# Power_Distribution_-_Display.net
KiCad netlist of a schematic drawn in Altium Designer
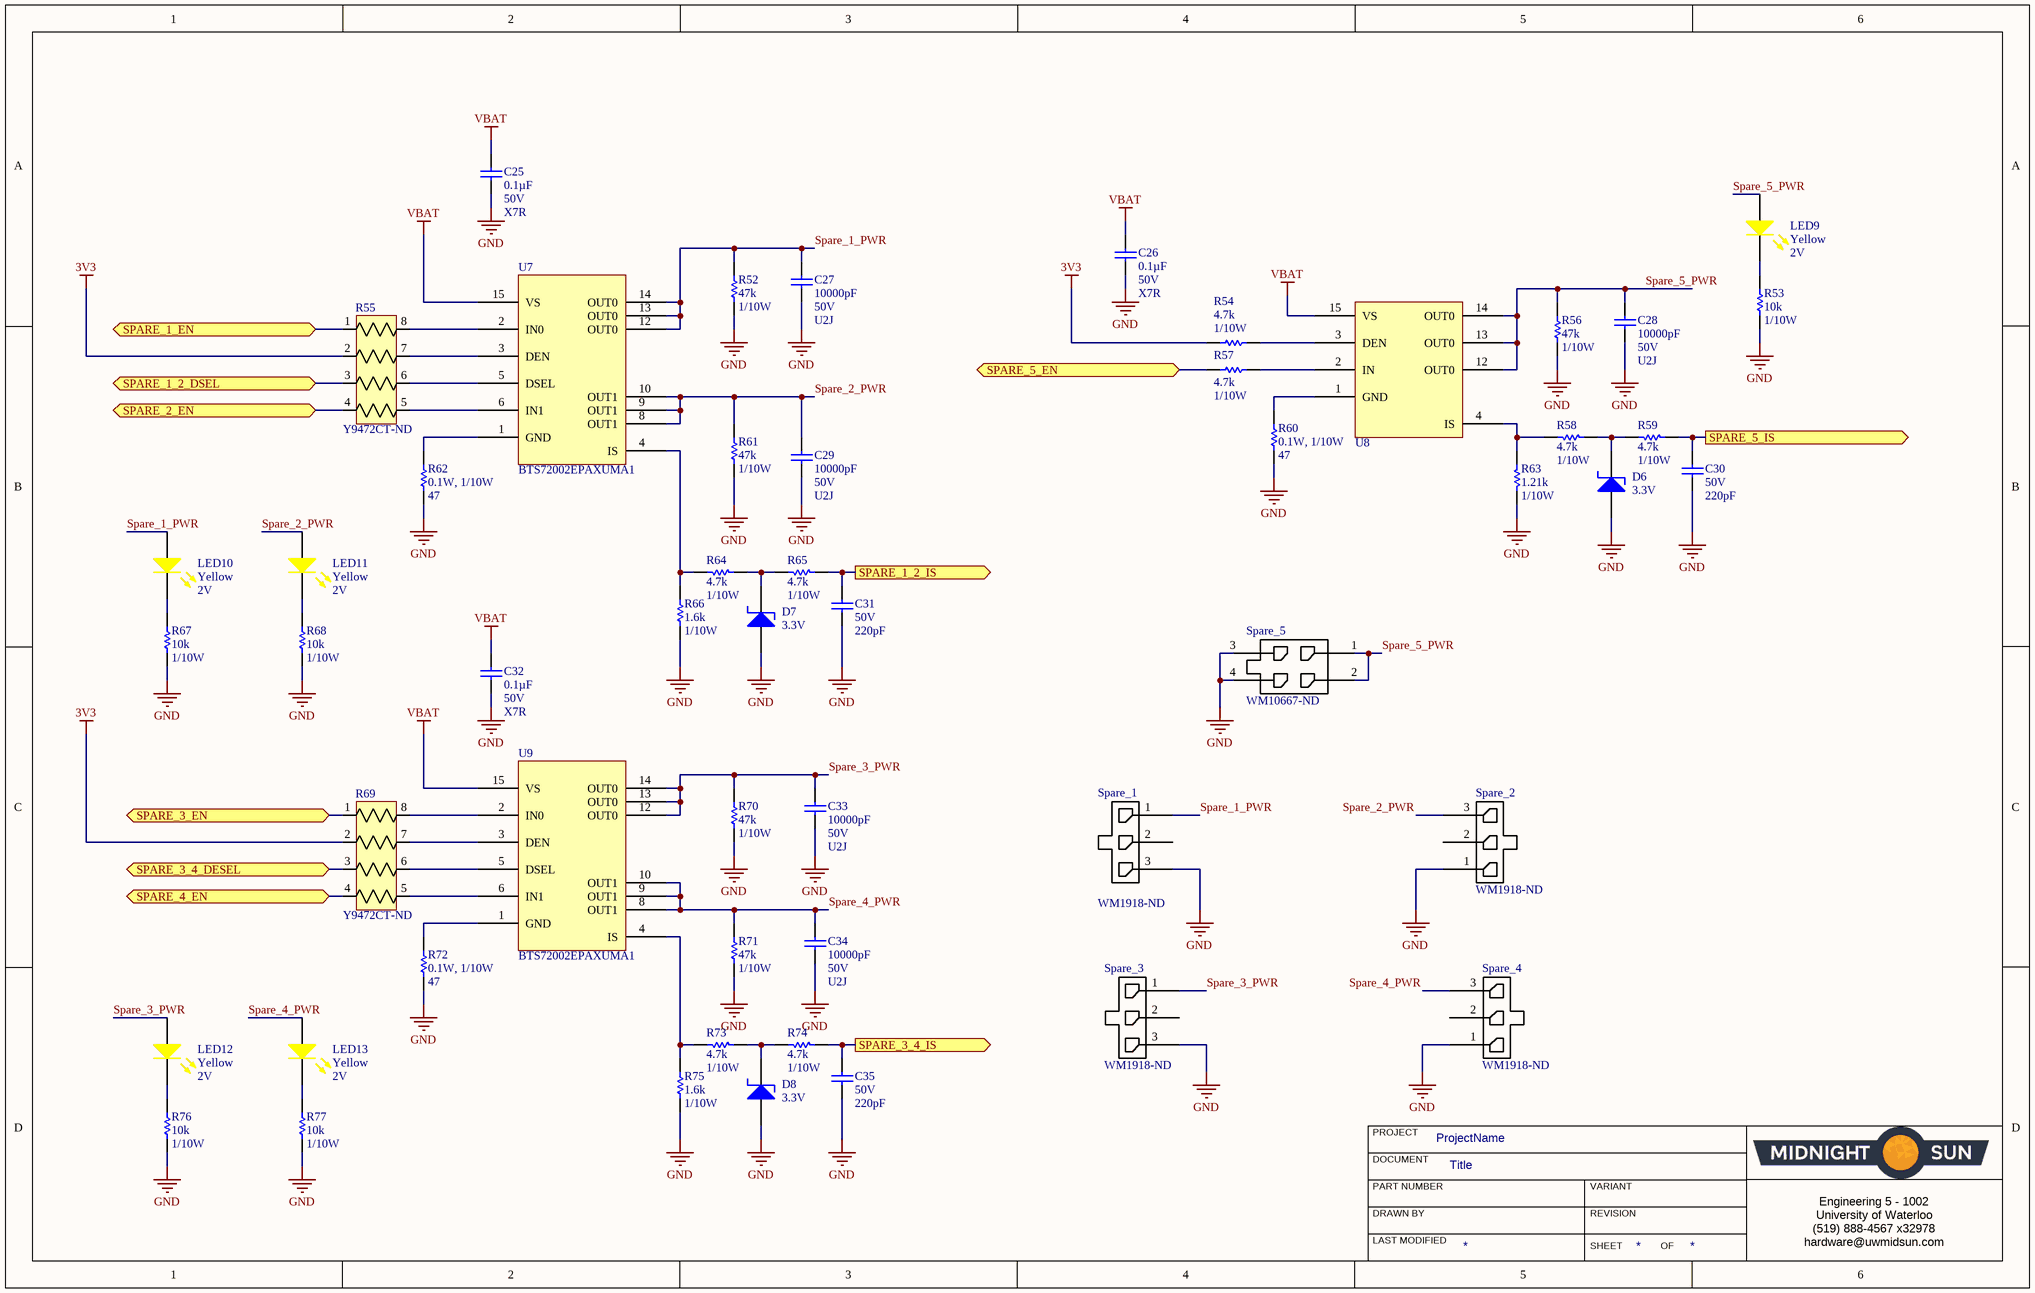
[diagram p0: Power Distribution - Display.SchDoc]

(export (version "E")
  (design (tool "Eeschema 10.0.6"))
  (components
    (comp (ref "C25")
      (value "CAP CER 0.1UF 50V 10% X7R 0603")
      (footprint "CAP, 0603")
      (description "0.10µF ±10% 50V Ceramic Capacitor X7R 0603 (1608 Metric)")
      (fields
        (field (name "TOLERANCE") "±10%")
        (field (name "CAPACITANCE") "0.1µF")
        (field (name "VOLTAGE") "50V")
        (field (name "TEMPERATURE COEFFICIENT") "X7R")
      )
      (libsource (lib "Schematic Diagrams") (part "CAP CER 0.1UF 50V 10% X7R 0603"))
    )
    (comp (ref "C26")
      (value "CAP CER 0.1UF 50V 10% X7R 0603")
      (footprint "CAP, 0603")
      (description "0.10µF ±10% 50V Ceramic Capacitor X7R 0603 (1608 Metric)")
      (fields
        (field (name "TOLERANCE") "±10%")
        (field (name "CAPACITANCE") "0.1µF")
        (field (name "VOLTAGE") "50V")
        (field (name "TEMPERATURE COEFFICIENT") "X7R")
      )
      (libsource (lib "Schematic Diagrams") (part "CAP CER 0.1UF 50V 10% X7R 0603"))
    )
    (comp (ref "C27")
      (value "CAP CER 10nF 50V 5% X7R 0603")
      (footprint "CAP, 0603")
      (description "10000pF ±5% 50V Ceramic Capacitor U2J 0603 (1608 Metric)")
      (fields
        (field (name "TOLERANCE") "±5%")
        (field (name "CAPACITANCE") "10000pF")
        (field (name "VOLTAGE") "50V")
        (field (name "TEMPERATURE COEFFICIENT") "U2J")
      )
      (libsource (lib "Schematic Diagrams") (part "CAP CER 10nF 50V 5% X7R 0603"))
    )
    (comp (ref "C28")
      (value "CAP CER 10nF 50V 5% X7R 0603")
      (footprint "CAP, 0603")
      (description "10000pF ±5% 50V Ceramic Capacitor U2J 0603 (1608 Metric)")
      (fields
        (field (name "TOLERANCE") "±5%")
        (field (name "CAPACITANCE") "10000pF")
        (field (name "VOLTAGE") "50V")
        (field (name "TEMPERATURE COEFFICIENT") "U2J")
      )
      (libsource (lib "Schematic Diagrams") (part "CAP CER 10nF 50V 5% X7R 0603"))
    )
    (comp (ref "C29")
      (value "CAP CER 10nF 50V 5% X7R 0603")
      (footprint "CAP, 0603")
      (description "10000pF ±5% 50V Ceramic Capacitor U2J 0603 (1608 Metric)")
      (fields
        (field (name "TOLERANCE") "±5%")
        (field (name "CAPACITANCE") "10000pF")
        (field (name "VOLTAGE") "50V")
        (field (name "TEMPERATURE COEFFICIENT") "U2J")
      )
      (libsource (lib "Schematic Diagrams") (part "CAP CER 10nF 50V 5% X7R 0603"))
    )
    (comp (ref "C30")
      (value "CAP CER 220PF 50V C0G/NP0 0603")
      (footprint "CAP, 0603")
      (description "220pF ±5% 50V Ceramic Capacitor C0G, NP0 0603 (1608 Metric)")
      (fields
        (field (name "MANUFACTURER") "KEMET")
        (field (name "TOLERANCE") "5%")
        (field (name "VOLTAGE RATING") "50V")
        (field (name "CAPACITANCE") "220pF")
      )
      (libsource (lib "Schematic Diagrams") (part "CAP CER 220PF 50V C0G/NP0 0603"))
    )
    (comp (ref "C31")
      (value "CAP CER 220PF 50V C0G/NP0 0603")
      (footprint "CAP, 0603")
      (description "220pF ±5% 50V Ceramic Capacitor C0G, NP0 0603 (1608 Metric)")
      (fields
        (field (name "MANUFACTURER") "KEMET")
        (field (name "TOLERANCE") "5%")
        (field (name "VOLTAGE RATING") "50V")
        (field (name "CAPACITANCE") "220pF")
      )
      (libsource (lib "Schematic Diagrams") (part "CAP CER 220PF 50V C0G/NP0 0603"))
    )
    (comp (ref "C32")
      (value "CAP CER 0.1UF 50V 10% X7R 0603")
      (footprint "CAP, 0603")
      (description "0.10µF ±10% 50V Ceramic Capacitor X7R 0603 (1608 Metric)")
      (fields
        (field (name "TOLERANCE") "±10%")
        (field (name "CAPACITANCE") "0.1µF")
        (field (name "VOLTAGE") "50V")
        (field (name "TEMPERATURE COEFFICIENT") "X7R")
      )
      (libsource (lib "Schematic Diagrams") (part "CAP CER 0.1UF 50V 10% X7R 0603"))
    )
    (comp (ref "C33")
      (value "CAP CER 10nF 50V 5% X7R 0603")
      (footprint "CAP, 0603")
      (description "10000pF ±5% 50V Ceramic Capacitor U2J 0603 (1608 Metric)")
      (fields
        (field (name "TOLERANCE") "±5%")
        (field (name "CAPACITANCE") "10000pF")
        (field (name "VOLTAGE") "50V")
        (field (name "TEMPERATURE COEFFICIENT") "U2J")
      )
      (libsource (lib "Schematic Diagrams") (part "CAP CER 10nF 50V 5% X7R 0603"))
    )
    (comp (ref "C34")
      (value "CAP CER 10nF 50V 5% X7R 0603")
      (footprint "CAP, 0603")
      (description "10000pF ±5% 50V Ceramic Capacitor U2J 0603 (1608 Metric)")
      (fields
        (field (name "TOLERANCE") "±5%")
        (field (name "CAPACITANCE") "10000pF")
        (field (name "VOLTAGE") "50V")
        (field (name "TEMPERATURE COEFFICIENT") "U2J")
      )
      (libsource (lib "Schematic Diagrams") (part "CAP CER 10nF 50V 5% X7R 0603"))
    )
    (comp (ref "C35")
      (value "CAP CER 220PF 50V C0G/NP0 0603")
      (footprint "CAP, 0603")
      (description "220pF ±5% 50V Ceramic Capacitor C0G, NP0 0603 (1608 Metric)")
      (fields
        (field (name "MANUFACTURER") "KEMET")
        (field (name "TOLERANCE") "5%")
        (field (name "VOLTAGE RATING") "50V")
        (field (name "CAPACITANCE") "220pF")
      )
      (libsource (lib "Schematic Diagrams") (part "CAP CER 220PF 50V C0G/NP0 0603"))
    )
    (comp (ref "D6")
      (value "DIODE ZENER 3.3V 200MW SOD323")
      (footprint "sod-323")
      (description "Zener Diode 3.3V 200mW ±5% Surface Mount SOD-323")
      (fields (field (name "VOLTAGE") "3.3V"))
      (libsource (lib "Schematic Diagrams") (part "DIODE ZENER 3.3V 200MW SOD323"))
    )
    (comp (ref "D7")
      (value "DIODE ZENER 3.3V 200MW SOD323")
      (footprint "sod-323")
      (description "Zener Diode 3.3V 200mW ±5% Surface Mount SOD-323")
      (fields (field (name "VOLTAGE") "3.3V"))
      (libsource (lib "Schematic Diagrams") (part "DIODE ZENER 3.3V 200MW SOD323"))
    )
    (comp (ref "D8")
      (value "DIODE ZENER 3.3V 200MW SOD323")
      (footprint "sod-323")
      (description "Zener Diode 3.3V 200mW ±5% Surface Mount SOD-323")
      (fields (field (name "VOLTAGE") "3.3V"))
      (libsource (lib "Schematic Diagrams") (part "DIODE ZENER 3.3V 200MW SOD323"))
    )
    (comp (ref "LED9")
      (value "LED YELLOW CLEAR 2.1V 0603")
      (footprint "LED_0603")
      (description "Yellow 590nm LED Indication - Discrete 2V 0603 (1608 Metric)")
      (fields
        (field (name "MANUFACTURER") "Wurth Electronics Inc.")
        (field (name "MANUFACTURER PART NUMBER") "150060YS75000")
        (field (name "COLOR") "Yellow")
        (field (name "VOLTAGE - FORWARD (VF) (TYP)") "2V")
      )
      (libsource (lib "Schematic Diagrams") (part "LED YELLOW CLEAR 2.1V 0603"))
    )
    (comp (ref "LED10")
      (value "LED YELLOW CLEAR 2.1V 0603")
      (footprint "LED_0603")
      (description "Yellow 590nm LED Indication - Discrete 2V 0603 (1608 Metric)")
      (fields
        (field (name "MANUFACTURER") "Wurth Electronics Inc.")
        (field (name "MANUFACTURER PART NUMBER") "150060YS75000")
        (field (name "COLOR") "Yellow")
        (field (name "VOLTAGE - FORWARD (VF) (TYP)") "2V")
      )
      (libsource (lib "Schematic Diagrams") (part "LED YELLOW CLEAR 2.1V 0603"))
    )
    (comp (ref "LED11")
      (value "LED YELLOW CLEAR 2.1V 0603")
      (footprint "LED_0603")
      (description "Yellow 590nm LED Indication - Discrete 2V 0603 (1608 Metric)")
      (fields
        (field (name "MANUFACTURER") "Wurth Electronics Inc.")
        (field (name "MANUFACTURER PART NUMBER") "150060YS75000")
        (field (name "COLOR") "Yellow")
        (field (name "VOLTAGE - FORWARD (VF) (TYP)") "2V")
      )
      (libsource (lib "Schematic Diagrams") (part "LED YELLOW CLEAR 2.1V 0603"))
    )
    (comp (ref "LED12")
      (value "LED YELLOW CLEAR 2.1V 0603")
      (footprint "LED_0603")
      (description "Yellow 590nm LED Indication - Discrete 2V 0603 (1608 Metric)")
      (fields
        (field (name "MANUFACTURER") "Wurth Electronics Inc.")
        (field (name "MANUFACTURER PART NUMBER") "150060YS75000")
        (field (name "COLOR") "Yellow")
        (field (name "VOLTAGE - FORWARD (VF) (TYP)") "2V")
      )
      (libsource (lib "Schematic Diagrams") (part "LED YELLOW CLEAR 2.1V 0603"))
    )
    (comp (ref "LED13")
      (value "LED YELLOW CLEAR 2.1V 0603")
      (footprint "LED_0603")
      (description "Yellow 590nm LED Indication - Discrete 2V 0603 (1608 Metric)")
      (fields
        (field (name "MANUFACTURER") "Wurth Electronics Inc.")
        (field (name "MANUFACTURER PART NUMBER") "150060YS75000")
        (field (name "COLOR") "Yellow")
        (field (name "VOLTAGE - FORWARD (VF) (TYP)") "2V")
      )
      (libsource (lib "Schematic Diagrams") (part "LED YELLOW CLEAR 2.1V 0603"))
    )
    (comp (ref "R52")
      (value "RES 47K OHM 1% 1/10W 0603")
      (footprint "RES, 0603")
      (description "47 kOhms ±1% 0.1W, 1/10W Chip Resistor 0603 (1608 Metric) Automotive AEC-Q200 Thick Film")
      (fields
        (field (name "MANUFACTURER") "Panasonic")
        (field (name "MANUFACTURER PART NUMBER") "ERJ3EKF4702V")
        (field (name "RESISTANCE") "47k")
        (field (name "POWER RATING") "1/10W")
      )
      (libsource (lib "Schematic Diagrams") (part "RES 47K OHM 1% 1/10W 0603"))
    )
    (comp (ref "R53")
      (value "RES 10K OHM 1% 1/10W 0603")
      (footprint "RES, 0603")
      (description "RES SMD 10K OHM 1% 1/10W 0603")
      (fields
        (field (name "TOLERANCE") "±1%")
        (field (name "RESISTANCE") "10k")
        (field (name "POWER") "1/10W")
      )
      (libsource (lib "Schematic Diagrams") (part "RES 10K OHM 1% 1/10W 0603"))
    )
    (comp (ref "R54")
      (value "RES 4.7K OHM 1% 1/10W 0603")
      (footprint "RES, 0603")
      (description "4.7k Ohm ±1% 0.1W, 1/10W Chip Resistor 0603 (1608 Metric) Moisture Resistant Thick Film")
      (fields
        (field (name "TOLERANCE") "±1%")
        (field (name "RESISTANCE (OHMS)") "4.7k")
        (field (name "POWER (WATTS)") "1/10W")
      )
      (libsource (lib "Schematic Diagrams") (part "RES 4.7K OHM 1% 1/10W 0603"))
    )
    (comp (ref "R55")
      (value "RES ARRAY 4 RES 4.7K OHM 1206")
      (footprint "RES ARRAY 4RES 1206")
      (fields (field (name "TOLERANCE") "±5%") (field (name "SUPPLIER PART NUMBER 1") "Y9472CT-ND"))
      (libsource (lib "Schematic Diagrams") (part "RES ARRAY 4 RES 4.7K OHM 1206"))
    )
    (comp (ref "R56")
      (value "RES 47K OHM 1% 1/10W 0603")
      (footprint "RES, 0603")
      (description "47 kOhms ±1% 0.1W, 1/10W Chip Resistor 0603 (1608 Metric) Automotive AEC-Q200 Thick Film")
      (fields
        (field (name "MANUFACTURER") "Panasonic")
        (field (name "MANUFACTURER PART NUMBER") "ERJ3EKF4702V")
        (field (name "RESISTANCE") "47k")
        (field (name "POWER RATING") "1/10W")
      )
      (libsource (lib "Schematic Diagrams") (part "RES 47K OHM 1% 1/10W 0603"))
    )
    (comp (ref "R57")
      (value "RES 4.7K OHM 1% 1/10W 0603")
      (footprint "RES, 0603")
      (description "4.7k Ohm ±1% 0.1W, 1/10W Chip Resistor 0603 (1608 Metric) Moisture Resistant Thick Film")
      (fields
        (field (name "TOLERANCE") "±1%")
        (field (name "RESISTANCE (OHMS)") "4.7k")
        (field (name "POWER (WATTS)") "1/10W")
      )
      (libsource (lib "Schematic Diagrams") (part "RES 4.7K OHM 1% 1/10W 0603"))
    )
    (comp (ref "R58")
      (value "RES 4.7K OHM 1% 1/10W 0603")
      (footprint "RES, 0603")
      (description "4.7k Ohm ±1% 0.1W, 1/10W Chip Resistor 0603 (1608 Metric) Moisture Resistant Thick Film")
      (fields
        (field (name "TOLERANCE") "±1%")
        (field (name "RESISTANCE (OHMS)") "4.7k")
        (field (name "POWER (WATTS)") "1/10W")
      )
      (libsource (lib "Schematic Diagrams") (part "RES 4.7K OHM 1% 1/10W 0603"))
    )
    (comp (ref "R59")
      (value "RES 4.7K OHM 1% 1/10W 0603")
      (footprint "RES, 0603")
      (description "4.7k Ohm ±1% 0.1W, 1/10W Chip Resistor 0603 (1608 Metric) Moisture Resistant Thick Film")
      (fields
        (field (name "TOLERANCE") "±1%")
        (field (name "RESISTANCE (OHMS)") "4.7k")
        (field (name "POWER (WATTS)") "1/10W")
      )
      (libsource (lib "Schematic Diagrams") (part "RES 4.7K OHM 1% 1/10W 0603"))
    )
    (comp (ref "R60")
      (value "RES SMD 47 OHM 1% 1/10W 0603")
      (footprint "RES, 0603")
      (fields
        (field (name "TOLERANCE") "±1%")
        (field (name "POWER (WATTS)") "0.1W, 1/10W")
        (field (name "VALUES") "47")
      )
      (libsource (lib "Schematic Diagrams") (part "RES SMD 47 OHM 1% 1/10W 0603"))
    )
    (comp (ref "R61")
      (value "RES 47K OHM 1% 1/10W 0603")
      (footprint "RES, 0603")
      (description "47 kOhms ±1% 0.1W, 1/10W Chip Resistor 0603 (1608 Metric) Automotive AEC-Q200 Thick Film")
      (fields
        (field (name "MANUFACTURER") "Panasonic")
        (field (name "MANUFACTURER PART NUMBER") "ERJ3EKF4702V")
        (field (name "RESISTANCE") "47k")
        (field (name "POWER RATING") "1/10W")
      )
      (libsource (lib "Schematic Diagrams") (part "RES 47K OHM 1% 1/10W 0603"))
    )
    (comp (ref "R62")
      (value "RES SMD 47 OHM 1% 1/10W 0603")
      (footprint "RES, 0603")
      (fields
        (field (name "TOLERANCE") "±1%")
        (field (name "POWER (WATTS)") "0.1W, 1/10W")
        (field (name "VALUES") "47")
      )
      (libsource (lib "Schematic Diagrams") (part "RES SMD 47 OHM 1% 1/10W 0603"))
    )
    (comp (ref "R63")
      (value "RES 1.21K OHM 1% 1/10W 0603")
      (footprint "RES, 0603")
      (description "1.21k Ohm ±1% 0.1W, 1/10W Chip Resistor 0603 (1608 Metric) Moisture Resistant Thick Film")
      (fields
        (field (name "TOLERANCE") "±1%")
        (field (name "RESISTANCE") "1.21k")
        (field (name "POWER") "1/10W")
      )
      (libsource (lib "Schematic Diagrams") (part "RES 1.21K OHM 1% 1/10W 0603"))
    )
    (comp (ref "R64")
      (value "RES 4.7K OHM 1% 1/10W 0603")
      (footprint "RES, 0603")
      (description "4.7k Ohm ±1% 0.1W, 1/10W Chip Resistor 0603 (1608 Metric) Moisture Resistant Thick Film")
      (fields
        (field (name "TOLERANCE") "±1%")
        (field (name "RESISTANCE (OHMS)") "4.7k")
        (field (name "POWER (WATTS)") "1/10W")
      )
      (libsource (lib "Schematic Diagrams") (part "RES 4.7K OHM 1% 1/10W 0603"))
    )
    (comp (ref "R65")
      (value "RES 4.7K OHM 1% 1/10W 0603")
      (footprint "RES, 0603")
      (description "4.7k Ohm ±1% 0.1W, 1/10W Chip Resistor 0603 (1608 Metric) Moisture Resistant Thick Film")
      (fields
        (field (name "TOLERANCE") "±1%")
        (field (name "RESISTANCE (OHMS)") "4.7k")
        (field (name "POWER (WATTS)") "1/10W")
      )
      (libsource (lib "Schematic Diagrams") (part "RES 4.7K OHM 1% 1/10W 0603"))
    )
    (comp (ref "R66")
      (value "RES 1.6K OHM 1% 1/10W 0603")
      (footprint "RES, 0603")
      (description "1.6 kOhms ±1% 0.1W, 1/10W Chip Resistor 0603 (1608 Metric) Moisture Resistant Thick Film")
      (fields
        (field (name "MANUFACTURER") "Yageo")
        (field (name "MANUFACTURER PART NUMBER") "RC0603FR-071K6L")
        (field (name "RESISTANCE") "1.6k")
        (field (name "POWER RATING") "1/10W")
      )
      (libsource (lib "Schematic Diagrams") (part "RES 1.6K OHM 1% 1/10W 0603"))
    )
    (comp (ref "R67")
      (value "RES 10K OHM 1% 1/10W 0603")
      (footprint "RES, 0603")
      (description "RES SMD 10K OHM 1% 1/10W 0603")
      (fields
        (field (name "TOLERANCE") "±1%")
        (field (name "RESISTANCE") "10k")
        (field (name "POWER") "1/10W")
      )
      (libsource (lib "Schematic Diagrams") (part "RES 10K OHM 1% 1/10W 0603"))
    )
    (comp (ref "R68")
      (value "RES 10K OHM 1% 1/10W 0603")
      (footprint "RES, 0603")
      (description "RES SMD 10K OHM 1% 1/10W 0603")
      (fields
        (field (name "TOLERANCE") "±1%")
        (field (name "RESISTANCE") "10k")
        (field (name "POWER") "1/10W")
      )
      (libsource (lib "Schematic Diagrams") (part "RES 10K OHM 1% 1/10W 0603"))
    )
    (comp (ref "R69")
      (value "RES ARRAY 4 RES 4.7K OHM 1206")
      (footprint "RES ARRAY 4RES 1206")
      (fields (field (name "TOLERANCE") "±5%") (field (name "SUPPLIER PART NUMBER 1") "Y9472CT-ND"))
      (libsource (lib "Schematic Diagrams") (part "RES ARRAY 4 RES 4.7K OHM 1206"))
    )
    (comp (ref "R70")
      (value "RES 47K OHM 1% 1/10W 0603")
      (footprint "RES, 0603")
      (description "47 kOhms ±1% 0.1W, 1/10W Chip Resistor 0603 (1608 Metric) Automotive AEC-Q200 Thick Film")
      (fields
        (field (name "MANUFACTURER") "Panasonic")
        (field (name "MANUFACTURER PART NUMBER") "ERJ3EKF4702V")
        (field (name "RESISTANCE") "47k")
        (field (name "POWER RATING") "1/10W")
      )
      (libsource (lib "Schematic Diagrams") (part "RES 47K OHM 1% 1/10W 0603"))
    )
    (comp (ref "R71")
      (value "RES 47K OHM 1% 1/10W 0603")
      (footprint "RES, 0603")
      (description "47 kOhms ±1% 0.1W, 1/10W Chip Resistor 0603 (1608 Metric) Automotive AEC-Q200 Thick Film")
      (fields
        (field (name "MANUFACTURER") "Panasonic")
        (field (name "MANUFACTURER PART NUMBER") "ERJ3EKF4702V")
        (field (name "RESISTANCE") "47k")
        (field (name "POWER RATING") "1/10W")
      )
      (libsource (lib "Schematic Diagrams") (part "RES 47K OHM 1% 1/10W 0603"))
    )
    (comp (ref "R72")
      (value "RES SMD 47 OHM 1% 1/10W 0603")
      (footprint "RES, 0603")
      (fields
        (field (name "TOLERANCE") "±1%")
        (field (name "POWER (WATTS)") "0.1W, 1/10W")
        (field (name "VALUES") "47")
      )
      (libsource (lib "Schematic Diagrams") (part "RES SMD 47 OHM 1% 1/10W 0603"))
    )
    (comp (ref "R73")
      (value "RES 4.7K OHM 1% 1/10W 0603")
      (footprint "RES, 0603")
      (description "4.7k Ohm ±1% 0.1W, 1/10W Chip Resistor 0603 (1608 Metric) Moisture Resistant Thick Film")
      (fields
        (field (name "TOLERANCE") "±1%")
        (field (name "RESISTANCE (OHMS)") "4.7k")
        (field (name "POWER (WATTS)") "1/10W")
      )
      (libsource (lib "Schematic Diagrams") (part "RES 4.7K OHM 1% 1/10W 0603"))
    )
    (comp (ref "R74")
      (value "RES 4.7K OHM 1% 1/10W 0603")
      (footprint "RES, 0603")
      (description "4.7k Ohm ±1% 0.1W, 1/10W Chip Resistor 0603 (1608 Metric) Moisture Resistant Thick Film")
      (fields
        (field (name "TOLERANCE") "±1%")
        (field (name "RESISTANCE (OHMS)") "4.7k")
        (field (name "POWER (WATTS)") "1/10W")
      )
      (libsource (lib "Schematic Diagrams") (part "RES 4.7K OHM 1% 1/10W 0603"))
    )
    (comp (ref "R75")
      (value "RES 1.6K OHM 1% 1/10W 0603")
      (footprint "RES, 0603")
      (description "1.6 kOhms ±1% 0.1W, 1/10W Chip Resistor 0603 (1608 Metric) Moisture Resistant Thick Film")
      (fields
        (field (name "MANUFACTURER") "Yageo")
        (field (name "MANUFACTURER PART NUMBER") "RC0603FR-071K6L")
        (field (name "RESISTANCE") "1.6k")
        (field (name "POWER RATING") "1/10W")
      )
      (libsource (lib "Schematic Diagrams") (part "RES 1.6K OHM 1% 1/10W 0603"))
    )
    (comp (ref "R76")
      (value "RES 10K OHM 1% 1/10W 0603")
      (footprint "RES, 0603")
      (description "RES SMD 10K OHM 1% 1/10W 0603")
      (fields
        (field (name "TOLERANCE") "±1%")
        (field (name "RESISTANCE") "10k")
        (field (name "POWER") "1/10W")
      )
      (libsource (lib "Schematic Diagrams") (part "RES 10K OHM 1% 1/10W 0603"))
    )
    (comp (ref "R77")
      (value "RES 10K OHM 1% 1/10W 0603")
      (footprint "RES, 0603")
      (description "RES SMD 10K OHM 1% 1/10W 0603")
      (fields
        (field (name "TOLERANCE") "±1%")
        (field (name "RESISTANCE") "10k")
        (field (name "POWER") "1/10W")
      )
      (libsource (lib "Schematic Diagrams") (part "RES 10K OHM 1% 1/10W 0603"))
    )
    (comp (ref "Spare_1")
      (value "CONN 3POS MICROFIT")
      (footprint "CONN, 3 POS MICROFIT")
      (description "Connector Header Through Hole 3 position 0.118\" (3.00mm)")
      (fields (field (name "SUPPLIER PART NUMBER 1") "WM1918-ND"))
      (libsource (lib "Schematic Diagrams") (part "CONN 3POS MICROFIT"))
    )
    (comp (ref "Spare_2")
      (value "CONN 3POS MICROFIT")
      (footprint "CONN, 3 POS MICROFIT")
      (description "Connector Header Through Hole 3 position 0.118\" (3.00mm)")
      (fields (field (name "SUPPLIER PART NUMBER 1") "WM1918-ND"))
      (libsource (lib "Schematic Diagrams") (part "CONN 3POS MICROFIT"))
    )
    (comp (ref "Spare_3")
      (value "CONN 3POS MICROFIT")
      (footprint "CONN, 3 POS MICROFIT")
      (description "Connector Header Through Hole 3 position 0.118\" (3.00mm)")
      (fields (field (name "SUPPLIER PART NUMBER 1") "WM1918-ND"))
      (libsource (lib "Schematic Diagrams") (part "CONN 3POS MICROFIT"))
    )
    (comp (ref "Spare_4")
      (value "CONN 3POS MICROFIT")
      (footprint "CONN, 3 POS MICROFIT")
      (description "Connector Header Through Hole 3 position 0.118\" (3.00mm)")
      (fields (field (name "SUPPLIER PART NUMBER 1") "WM1918-ND"))
      (libsource (lib "Schematic Diagrams") (part "CONN 3POS MICROFIT"))
    )
    (comp (ref "Spare_5")
      (value "CONN 4POS MICRO-FIT 3mm")
      (footprint "CONN 4POS MICROFIT (2x2)")
      (fields
        (field (name "MANUFACTURER") "Molex, LLC")
        (field (name "MANUFACTURER PART NUMBER") "430450427")
        (field (name "SUPPLIER PART NUMBER 1") "WM10667-ND")
      )
      (libsource (lib "Schematic Diagrams") (part "CONN 4POS MICRO-FIT 3mm"))
    )
    (comp (ref "U7")
      (value "IC LOAD SWITCH BTS7200-2EPA PG-TSDSO-14_1")
      (footprint "IC LOAD SWITCH PG-TSDSO-14-22")
      (description "Power Switch/Driver 1:1 N-Channel 1.2A PG-TSDSO-14-22")
      (fields
        (field (name "MANUFACTURER") "Infineon")
        (field (name "MANUFACTURER PART NUMBER") "BTS72002EPAXUMA1")
      )
      (libsource (lib "Schematic Diagrams") (part "IC LOAD SWITCH BTS7200-2EPA PG-TSDSO-14_1"))
    )
    (comp (ref "U8")
      (value "IC LOAD SWITCH BTS70401EPA PG-TSDSO-14-22")
      (footprint "IC LOAD SWITCH PG-TSDSO-14-22")
      (description "Power Switch/Driver 1:1 N-Channel 4.5A PG-TSDSO-14-22")
      (fields
        (field (name "MANUFACTURER") "Infineon")
        (field (name "MANUFACTURER PART NUMBER") "BTS70401EPAXUMA1")
      )
      (libsource (lib "Schematic Diagrams") (part "IC LOAD SWITCH BTS70401EPA PG-TSDSO-14-22"))
    )
    (comp (ref "U9")
      (value "IC LOAD SWITCH BTS7200-2EPA PG-TSDSO-14_1")
      (footprint "IC LOAD SWITCH PG-TSDSO-14-22")
      (description "Power Switch/Driver 1:1 N-Channel 1.2A PG-TSDSO-14-22")
      (fields
        (field (name "MANUFACTURER") "Infineon")
        (field (name "MANUFACTURER PART NUMBER") "BTS72002EPAXUMA1")
      )
      (libsource (lib "Schematic Diagrams") (part "IC LOAD SWITCH BTS7200-2EPA PG-TSDSO-14_1"))
    )
  )
  (nets
    (net (code "1") (name "/SPARE_1_2_DSEL") (class "Default")
      (node (ref "R55") (pin "3") (pinfunction "3_3") (pintype "passive"))
    )
    (net (code "2") (name "/SPARE_1_2_IS") (class "Default")
      (node (ref "C31") (pin "1") (pinfunction "1_1") (pintype "passive"))
      (node (ref "R65") (pin "1") (pinfunction "1_1") (pintype "passive"))
    )
    (net (code "3") (name "/SPARE_1_EN") (class "Default")
      (node (ref "R55") (pin "1") (pinfunction "1_1") (pintype "passive"))
    )
    (net (code "4") (name "/SPARE_2_EN") (class "Default")
      (node (ref "R55") (pin "4") (pinfunction "4_4") (pintype "passive"))
    )
    (net (code "5") (name "/SPARE_3_4_DESEL") (class "Default")
      (node (ref "R69") (pin "3") (pinfunction "3_3") (pintype "passive"))
    )
    (net (code "6") (name "/SPARE_3_4_IS") (class "Default")
      (node (ref "C35") (pin "1") (pinfunction "1_1") (pintype "passive"))
      (node (ref "R74") (pin "1") (pinfunction "1_1") (pintype "passive"))
    )
    (net (code "7") (name "/SPARE_3_EN") (class "Default")
      (node (ref "R69") (pin "1") (pinfunction "1_1") (pintype "passive"))
    )
    (net (code "8") (name "/SPARE_4_EN") (class "Default")
      (node (ref "R69") (pin "4") (pinfunction "4_4") (pintype "passive"))
    )
    (net (code "9") (name "/SPARE_5_EN") (class "Default")
      (node (ref "R57") (pin "1") (pinfunction "1_1") (pintype "passive"))
    )
    (net (code "10") (name "/SPARE_5_IS") (class "Default")
      (node (ref "C30") (pin "1") (pinfunction "1_1") (pintype "passive"))
      (node (ref "R59") (pin "1") (pinfunction "1_1") (pintype "passive"))
    )
    (net (code "11") (name "/Spare_1_PWR") (class "Default")
      (node (ref "C27") (pin "1") (pinfunction "1_1") (pintype "passive"))
      (node (ref "LED10") (pin "1") (pinfunction "A_1") (pintype "passive"))
      (node (ref "R52") (pin "1") (pinfunction "1_1") (pintype "passive"))
      (node (ref "Spare_1") (pin "1") (pinfunction "1_1") (pintype "passive"))
      (node (ref "U7") (pin "12") (pinfunction "OUT0_12") (pintype "passive"))
      (node (ref "U7") (pin "13") (pinfunction "OUT0_13") (pintype "passive"))
      (node (ref "U7") (pin "14") (pinfunction "OUT0_14") (pintype "passive"))
    )
    (net (code "12") (name "/Spare_2_PWR") (class "Default")
      (node (ref "C29") (pin "1") (pinfunction "1_1") (pintype "passive"))
      (node (ref "LED11") (pin "1") (pinfunction "A_1") (pintype "passive"))
      (node (ref "R61") (pin "1") (pinfunction "1_1") (pintype "passive"))
      (node (ref "Spare_2") (pin "3") (pinfunction "3_3") (pintype "passive"))
      (node (ref "U7") (pin "10") (pinfunction "OUT1_10") (pintype "passive"))
      (node (ref "U7") (pin "8") (pinfunction "OUT1_8") (pintype "passive"))
      (node (ref "U7") (pin "9") (pinfunction "OUT1_9") (pintype "passive"))
    )
    (net (code "13") (name "/Spare_3_PWR") (class "Default")
      (node (ref "C33") (pin "1") (pinfunction "1_1") (pintype "passive"))
      (node (ref "LED12") (pin "1") (pinfunction "A_1") (pintype "passive"))
      (node (ref "R70") (pin "1") (pinfunction "1_1") (pintype "passive"))
      (node (ref "Spare_3") (pin "1") (pinfunction "1_1") (pintype "passive"))
      (node (ref "U9") (pin "12") (pinfunction "OUT0_12") (pintype "passive"))
      (node (ref "U9") (pin "13") (pinfunction "OUT0_13") (pintype "passive"))
      (node (ref "U9") (pin "14") (pinfunction "OUT0_14") (pintype "passive"))
    )
    (net (code "14") (name "/Spare_4_PWR") (class "Default")
      (node (ref "C34") (pin "1") (pinfunction "1_1") (pintype "passive"))
      (node (ref "LED13") (pin "1") (pinfunction "A_1") (pintype "passive"))
      (node (ref "R71") (pin "1") (pinfunction "1_1") (pintype "passive"))
      (node (ref "Spare_4") (pin "3") (pinfunction "3_3") (pintype "passive"))
      (node (ref "U9") (pin "10") (pinfunction "OUT1_10") (pintype "passive"))
      (node (ref "U9") (pin "8") (pinfunction "OUT1_8") (pintype "passive"))
      (node (ref "U9") (pin "9") (pinfunction "OUT1_9") (pintype "passive"))
    )
    (net (code "15") (name "/Spare_5_PWR") (class "Default")
      (node (ref "C28") (pin "1") (pinfunction "1_1") (pintype "passive"))
      (node (ref "LED9") (pin "1") (pinfunction "A_1") (pintype "passive"))
      (node (ref "R56") (pin "1") (pinfunction "1_1") (pintype "passive"))
      (node (ref "Spare_5") (pin "1") (pinfunction "1_1") (pintype "passive"))
      (node (ref "Spare_5") (pin "2") (pinfunction "2_2") (pintype "passive"))
      (node (ref "U8") (pin "12") (pinfunction "OUT0_12") (pintype "passive"))
      (node (ref "U8") (pin "13") (pinfunction "OUT0_13") (pintype "passive"))
      (node (ref "U8") (pin "14") (pinfunction "OUT0_14") (pintype "passive"))
    )
    (net (code "16") (name "3V3") (class "Default")
      (node (ref "R54") (pin "1") (pinfunction "1_1") (pintype "passive"))
      (node (ref "R55") (pin "2") (pinfunction "2_2") (pintype "passive"))
      (node (ref "R69") (pin "2") (pinfunction "2_2") (pintype "passive"))
    )
    (net (code "17") (name "GND") (class "Default")
      (node (ref "C25") (pin "2") (pinfunction "2_2") (pintype "passive"))
      (node (ref "C26") (pin "2") (pinfunction "2_2") (pintype "passive"))
      (node (ref "C27") (pin "2") (pinfunction "2_2") (pintype "passive"))
      (node (ref "C28") (pin "2") (pinfunction "2_2") (pintype "passive"))
      (node (ref "C29") (pin "2") (pinfunction "2_2") (pintype "passive"))
      (node (ref "C30") (pin "2") (pinfunction "2_2") (pintype "passive"))
      (node (ref "C31") (pin "2") (pinfunction "2_2") (pintype "passive"))
      (node (ref "C32") (pin "2") (pinfunction "2_2") (pintype "passive"))
      (node (ref "C33") (pin "2") (pinfunction "2_2") (pintype "passive"))
      (node (ref "C34") (pin "2") (pinfunction "2_2") (pintype "passive"))
      (node (ref "C35") (pin "2") (pinfunction "2_2") (pintype "passive"))
      (node (ref "D6") (pin "1") (pinfunction "A_1") (pintype "passive"))
      (node (ref "D7") (pin "1") (pinfunction "A_1") (pintype "passive"))
      (node (ref "D8") (pin "1") (pinfunction "A_1") (pintype "passive"))
      (node (ref "R52") (pin "2") (pinfunction "2_2") (pintype "passive"))
      (node (ref "R53") (pin "2") (pinfunction "2_2") (pintype "passive"))
      (node (ref "R56") (pin "2") (pinfunction "2_2") (pintype "passive"))
      (node (ref "R60") (pin "2") (pinfunction "2_2") (pintype "passive"))
      (node (ref "R61") (pin "2") (pinfunction "2_2") (pintype "passive"))
      (node (ref "R62") (pin "2") (pinfunction "2_2") (pintype "passive"))
      (node (ref "R63") (pin "2") (pinfunction "2_2") (pintype "passive"))
      (node (ref "R66") (pin "2") (pinfunction "2_2") (pintype "passive"))
      (node (ref "R67") (pin "2") (pinfunction "2_2") (pintype "passive"))
      (node (ref "R68") (pin "2") (pinfunction "2_2") (pintype "passive"))
      (node (ref "R70") (pin "2") (pinfunction "2_2") (pintype "passive"))
      (node (ref "R71") (pin "2") (pinfunction "2_2") (pintype "passive"))
      (node (ref "R72") (pin "2") (pinfunction "2_2") (pintype "passive"))
      (node (ref "R75") (pin "2") (pinfunction "2_2") (pintype "passive"))
      (node (ref "R76") (pin "2") (pinfunction "2_2") (pintype "passive"))
      (node (ref "R77") (pin "2") (pinfunction "2_2") (pintype "passive"))
      (node (ref "Spare_1") (pin "3") (pinfunction "3_3") (pintype "passive"))
      (node (ref "Spare_2") (pin "1") (pinfunction "1_1") (pintype "passive"))
      (node (ref "Spare_3") (pin "3") (pinfunction "3_3") (pintype "passive"))
      (node (ref "Spare_4") (pin "1") (pinfunction "1_1") (pintype "passive"))
      (node (ref "Spare_5") (pin "3") (pinfunction "3_3") (pintype "passive"))
      (node (ref "Spare_5") (pin "4") (pinfunction "4_4") (pintype "passive"))
    )
    (net (code "18") (name "Net-(D6-K)") (class "Default")
      (node (ref "D6") (pin "2") (pinfunction "K_2") (pintype "passive"))
      (node (ref "R58") (pin "1") (pinfunction "1_1") (pintype "passive"))
      (node (ref "R59") (pin "2") (pinfunction "2_2") (pintype "passive"))
    )
    (net (code "19") (name "Net-(D7-K)") (class "Default")
      (node (ref "D7") (pin "2") (pinfunction "K_2") (pintype "passive"))
      (node (ref "R64") (pin "1") (pinfunction "1_1") (pintype "passive"))
      (node (ref "R65") (pin "2") (pinfunction "2_2") (pintype "passive"))
    )
    (net (code "20") (name "Net-(D8-K)") (class "Default")
      (node (ref "D8") (pin "2") (pinfunction "K_2") (pintype "passive"))
      (node (ref "R73") (pin "1") (pinfunction "1_1") (pintype "passive"))
      (node (ref "R74") (pin "2") (pinfunction "2_2") (pintype "passive"))
    )
    (net (code "21") (name "Net-(LED9-K)") (class "Default")
      (node (ref "LED9") (pin "2") (pinfunction "K_2") (pintype "passive"))
      (node (ref "R53") (pin "1") (pinfunction "1_1") (pintype "passive"))
    )
    (net (code "22") (name "Net-(LED10-K)") (class "Default")
      (node (ref "LED10") (pin "2") (pinfunction "K_2") (pintype "passive"))
      (node (ref "R67") (pin "1") (pinfunction "1_1") (pintype "passive"))
    )
    (net (code "23") (name "Net-(LED11-K)") (class "Default")
      (node (ref "LED11") (pin "2") (pinfunction "K_2") (pintype "passive"))
      (node (ref "R68") (pin "1") (pinfunction "1_1") (pintype "passive"))
    )
    (net (code "24") (name "Net-(LED12-K)") (class "Default")
      (node (ref "LED12") (pin "2") (pinfunction "K_2") (pintype "passive"))
      (node (ref "R76") (pin "1") (pinfunction "1_1") (pintype "passive"))
    )
    (net (code "25") (name "Net-(LED13-K)") (class "Default")
      (node (ref "LED13") (pin "2") (pinfunction "K_2") (pintype "passive"))
      (node (ref "R77") (pin "1") (pinfunction "1_1") (pintype "passive"))
    )
    (net (code "26") (name "Net-(U7-DEN)") (class "Default")
      (node (ref "R55") (pin "7") (pinfunction "7_7") (pintype "passive"))
      (node (ref "U7") (pin "3") (pinfunction "DEN_3") (pintype "passive"))
    )
    (net (code "27") (name "Net-(U7-DSEL)") (class "Default")
      (node (ref "R55") (pin "6") (pinfunction "6_6") (pintype "passive"))
      (node (ref "U7") (pin "5") (pinfunction "DSEL_5") (pintype "passive"))
    )
    (net (code "28") (name "Net-(U7-GND)") (class "Default")
      (node (ref "R62") (pin "1") (pinfunction "1_1") (pintype "passive"))
      (node (ref "U7") (pin "1") (pinfunction "GND_1") (pintype "passive"))
    )
    (net (code "29") (name "Net-(U7-IN0)") (class "Default")
      (node (ref "R55") (pin "8") (pinfunction "8_8") (pintype "passive"))
      (node (ref "U7") (pin "2") (pinfunction "IN0_2") (pintype "passive"))
    )
    (net (code "30") (name "Net-(U7-IN1)") (class "Default")
      (node (ref "R55") (pin "5") (pinfunction "5_5") (pintype "passive"))
      (node (ref "U7") (pin "6") (pinfunction "IN1_6") (pintype "passive"))
    )
    (net (code "31") (name "Net-(U7-IS)") (class "Default")
      (node (ref "R64") (pin "2") (pinfunction "2_2") (pintype "passive"))
      (node (ref "R66") (pin "1") (pinfunction "1_1") (pintype "passive"))
      (node (ref "U7") (pin "4") (pinfunction "IS_4") (pintype "passive"))
    )
    (net (code "32") (name "Net-(U8-DEN)") (class "Default")
      (node (ref "R54") (pin "2") (pinfunction "2_2") (pintype "passive"))
      (node (ref "U8") (pin "3") (pinfunction "DEN_3") (pintype "passive"))
    )
    (net (code "33") (name "Net-(U8-GND)") (class "Default")
      (node (ref "R60") (pin "1") (pinfunction "1_1") (pintype "passive"))
      (node (ref "U8") (pin "1") (pinfunction "GND_1") (pintype "passive"))
    )
    (net (code "34") (name "Net-(U8-IN)") (class "Default")
      (node (ref "R57") (pin "2") (pinfunction "2_2") (pintype "passive"))
      (node (ref "U8") (pin "2") (pinfunction "IN_2") (pintype "passive"))
    )
    (net (code "35") (name "Net-(U8-IS)") (class "Default")
      (node (ref "R58") (pin "2") (pinfunction "2_2") (pintype "passive"))
      (node (ref "R63") (pin "1") (pinfunction "1_1") (pintype "passive"))
      (node (ref "U8") (pin "4") (pinfunction "IS_4") (pintype "passive"))
    )
    (net (code "36") (name "Net-(U9-DEN)") (class "Default")
      (node (ref "R69") (pin "7") (pinfunction "7_7") (pintype "passive"))
      (node (ref "U9") (pin "3") (pinfunction "DEN_3") (pintype "passive"))
    )
    (net (code "37") (name "Net-(U9-DSEL)") (class "Default")
      (node (ref "R69") (pin "6") (pinfunction "6_6") (pintype "passive"))
      (node (ref "U9") (pin "5") (pinfunction "DSEL_5") (pintype "passive"))
    )
    (net (code "38") (name "Net-(U9-GND)") (class "Default")
      (node (ref "R72") (pin "1") (pinfunction "1_1") (pintype "passive"))
      (node (ref "U9") (pin "1") (pinfunction "GND_1") (pintype "passive"))
    )
    (net (code "39") (name "Net-(U9-IN0)") (class "Default")
      (node (ref "R69") (pin "8") (pinfunction "8_8") (pintype "passive"))
      (node (ref "U9") (pin "2") (pinfunction "IN0_2") (pintype "passive"))
    )
    (net (code "40") (name "Net-(U9-IN1)") (class "Default")
      (node (ref "R69") (pin "5") (pinfunction "5_5") (pintype "passive"))
      (node (ref "U9") (pin "6") (pinfunction "IN1_6") (pintype "passive"))
    )
    (net (code "41") (name "Net-(U9-IS)") (class "Default")
      (node (ref "R73") (pin "2") (pinfunction "2_2") (pintype "passive"))
      (node (ref "R75") (pin "1") (pinfunction "1_1") (pintype "passive"))
      (node (ref "U9") (pin "4") (pinfunction "IS_4") (pintype "passive"))
    )
    (net (code "42") (name "VBAT") (class "Default")
      (node (ref "C25") (pin "1") (pinfunction "1_1") (pintype "passive"))
      (node (ref "C26") (pin "1") (pinfunction "1_1") (pintype "passive"))
      (node (ref "C32") (pin "1") (pinfunction "1_1") (pintype "passive"))
      (node (ref "U7") (pin "15") (pinfunction "VS_15") (pintype "passive"))
      (node (ref "U8") (pin "15") (pinfunction "VS_15") (pintype "passive"))
      (node (ref "U9") (pin "15") (pinfunction "VS_15") (pintype "passive"))
    )
    (net (code "43") (name "unconnected-(Spare_1-21-Pad2)") (class "Default")
      (node (ref "Spare_1") (pin "2") (pinfunction "21_2") (pintype "passive"))
    )
    (net (code "44") (name "unconnected-(Spare_2-21-Pad2)") (class "Default")
      (node (ref "Spare_2") (pin "2") (pinfunction "21_2") (pintype "passive"))
    )
    (net (code "45") (name "unconnected-(Spare_3-21-Pad2)") (class "Default")
      (node (ref "Spare_3") (pin "2") (pinfunction "21_2") (pintype "passive"))
    )
    (net (code "46") (name "unconnected-(Spare_4-21-Pad2)") (class "Default")
      (node (ref "Spare_4") (pin "2") (pinfunction "21_2") (pintype "passive"))
    )
  )
)
